# RTC_1307.net
KiCad netlist of a schematic drawn in Altium Designer
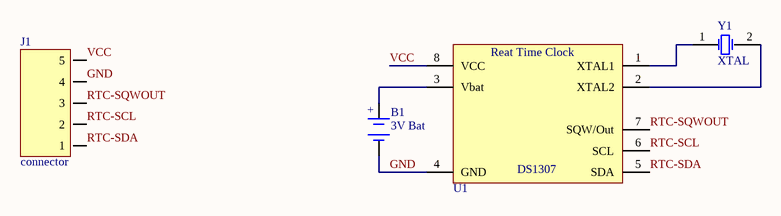
[diagram p0: RTC 1307.SchDoc]

(export (version "E")
  (design (tool "Eeschema 10.0.6"))
  (components
    (comp (ref "B1")
      (value "3V Bat")
      (footprint "PowerAdjusment:CR2032 DIP")
      (description "Battery")
      (libsource (lib "PowerAdjusment") (part "Battery"))
    )
    (comp (ref "J1")
      (value "connector")
      (footprint "Connector:Line 2.54 x 5")
      (description "Vert, Sgl line, Male")
      (libsource (lib "Connector") (part "PLS-5"))
    )
    (comp (ref "U1")
      (value "DS1307")
      (footprint "GeneralCases:DIP-8")
      (description "(RTC) Real Time Clock")
      (libsource (lib "Chips") (part "RTC DS1307"))
    )
    (comp (ref "Y1")
      (value "XTAL")
      (footprint "PassiveComponents:XTAL - Clock R")
      (description "Crystal Oscillator")
      (fields (field (name "PUBLISHER") "Altium Limited"))
      (libsource (lib "PassiveComponents") (part "XTAL"))
    )
  )
  (nets
    (net (code "1") (name "/GND") (class "Default")
      (node (ref "B1") (pin "2") (pinfunction "GND_2") (pintype "passive"))
      (node (ref "J1") (pin "4") (pinfunction "4_4") (pintype "passive"))
      (node (ref "U1") (pin "4") (pinfunction "GND_4") (pintype "passive"))
    )
    (net (code "2") (name "/RTC-SCL") (class "Default")
      (node (ref "J1") (pin "2") (pinfunction "2_2") (pintype "passive"))
      (node (ref "U1") (pin "6") (pinfunction "SCL_6") (pintype "tri_state"))
    )
    (net (code "3") (name "/RTC-SDA") (class "Default")
      (node (ref "J1") (pin "1") (pinfunction "1_1") (pintype "passive"))
      (node (ref "U1") (pin "5") (pinfunction "SDA_5") (pintype "tri_state"))
    )
    (net (code "4") (name "/RTC-SQWOUT") (class "Default")
      (node (ref "J1") (pin "3") (pinfunction "3_3") (pintype "passive"))
      (node (ref "U1") (pin "7") (pinfunction "SQW/Out_7") (pintype "tri_state"))
    )
    (net (code "5") (name "/VCC") (class "Default")
      (node (ref "J1") (pin "5") (pinfunction "5_5") (pintype "passive"))
      (node (ref "U1") (pin "8") (pinfunction "VCC_8") (pintype "power_in"))
    )
    (net (code "6") (name "Net-(B1-VC)") (class "Default")
      (node (ref "B1") (pin "1") (pinfunction "VC_1") (pintype "passive"))
      (node (ref "U1") (pin "3") (pinfunction "Vbat_3") (pintype "passive"))
    )
    (net (code "7") (name "Net-(U1-XTAL1)") (class "Default")
      (node (ref "U1") (pin "1") (pinfunction "XTAL1_1") (pintype "power_in"))
      (node (ref "Y1") (pin "1") (pinfunction "OSC1_1") (pintype "passive"))
    )
    (net (code "8") (name "Net-(U1-XTAL2)") (class "Default")
      (node (ref "U1") (pin "2") (pinfunction "XTAL2_2") (pintype "tri_state"))
      (node (ref "Y1") (pin "2") (pinfunction "OSC2_2") (pintype "passive"))
    )
  )
)
